# Connectors.net
KiCad netlist of a schematic drawn in Altium Designer
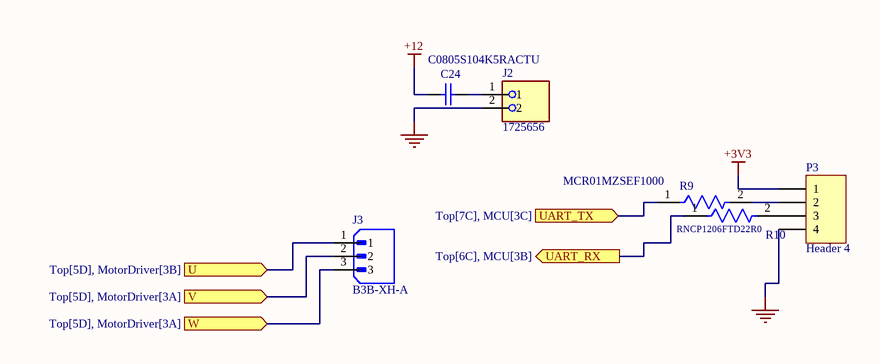
[diagram p0: Connectors.SchDoc]

(export (version "E")
  (design (tool "Eeschema 10.0.6"))
  (components
    (comp (ref "C24")
      (value "C0805S104K5RACTU")
      (footprint "CAPC2013X145X50NL20T25")
      (fields (field (name "MANUFACTURER") "Kemet"))
      (libsource (lib "Altium Content Vault") (part "CAP"))
    )
    (comp (ref "J2")
      (value "1725656")
      (footprint "PHOENIX_1725656")
      (description "PCB Terminal Screw 2.54mm 20AWG 160V 6A 2 Position COMBICON MPT Series ¦ Phoenix Contact 1725656")
      (fields (field (name "MF") "Phoenix Contact"))
      (libsource (lib "1725656") (part "1725656"))
    )
    (comp (ref "J3")
      (value "B3B-XH-A")
      (footprint "JST_B3B-XH-A")
      (description "Connector Header Through Hole 3 position 0.098 (2.50mm)")
      (fields (field (name "MF") "JST Sales"))
      (libsource (lib "B3B-XH-A") (part "B3B-XH-A"))
    )
    (comp (ref "P3")
      (value "Header 4")
      (footprint "HDR1X4")
      (description "Header, 4-Pin")
      (fields (field (name "PUBLISHER") "Altium Limited"))
      (libsource (lib "Miscellaneous Connectors") (part "Header 4"))
    )
    (comp (ref "R9")
      (value "MCR01MZSEF1000")
      (footprint "FP-MCR01-MFG")
      (description "Thick Film Chip Resistor, 0402, 100Ω, 1%, 100ppm/°C, 0.063W, 50V")
      (libsource (lib "Altium Content Vault") (part "1029c3af85768c4190bb7ad29bc67b5"))
    )
    (comp (ref "R10")
      (value "RNCP1206FTD22R0")
      (footprint "FP-RNCP1206-MFG")
      (description "22Ω ±1% 0.5W 1206 High Power Anti-Sulfur Thin Film Chip Resistor")
      (fields (field (name "TOLERANCE") "1%"))
      (libsource (lib "Altium Content Vault") (part "1029c3af85768c4190bb7ad29bc67b5"))
    )
  )
  (nets
    (net (code "1") (name "+3V3") (class "Default")
      (node (ref "P3") (pin "1") (pinfunction "1_1") (pintype "passive"))
    )
    (net (code "2") (name "+12") (class "Default")
      (node (ref "C24") (pin "1") (pinfunction "1_1") (pintype "passive"))
    )
    (net (code "3") (name "/U") (class "Default")
      (node (ref "J3") (pin "1") (pinfunction "1_1") (pintype "passive"))
    )
    (net (code "4") (name "/UART_RX") (class "Default")
      (node (ref "R10") (pin "1") (pinfunction "1_1") (pintype "passive"))
    )
    (net (code "5") (name "/UART_TX") (class "Default")
      (node (ref "R9") (pin "1") (pinfunction "1_1") (pintype "passive"))
    )
    (net (code "6") (name "/V") (class "Default")
      (node (ref "J3") (pin "2") (pinfunction "2_2") (pintype "passive"))
    )
    (net (code "7") (name "/W") (class "Default")
      (node (ref "J3") (pin "3") (pinfunction "3_3") (pintype "passive"))
    )
    (net (code "8") (name "<NO NET>") (class "Default")
      (node (ref "J2") (pin "2") (pinfunction "2_2") (pintype "passive"))
      (node (ref "P3") (pin "4") (pinfunction "4_4") (pintype "passive"))
    )
    (net (code "9") (name "Net-(C24-Pad2)") (class "Default")
      (node (ref "C24") (pin "2") (pinfunction "2_2") (pintype "passive"))
      (node (ref "J2") (pin "1") (pinfunction "1_1") (pintype "passive"))
    )
    (net (code "10") (name "Net-(P3-Pad2)") (class "Default")
      (node (ref "P3") (pin "2") (pinfunction "2_2") (pintype "passive"))
      (node (ref "R9") (pin "2") (pinfunction "2_2") (pintype "passive"))
    )
    (net (code "11") (name "Net-(P3-Pad3)") (class "Default")
      (node (ref "P3") (pin "3") (pinfunction "3_3") (pintype "passive"))
      (node (ref "R10") (pin "2") (pinfunction "2_2") (pintype "passive"))
    )
  )
)
